# design.net
KiCad netlist of a schematic drawn in Altium Designer
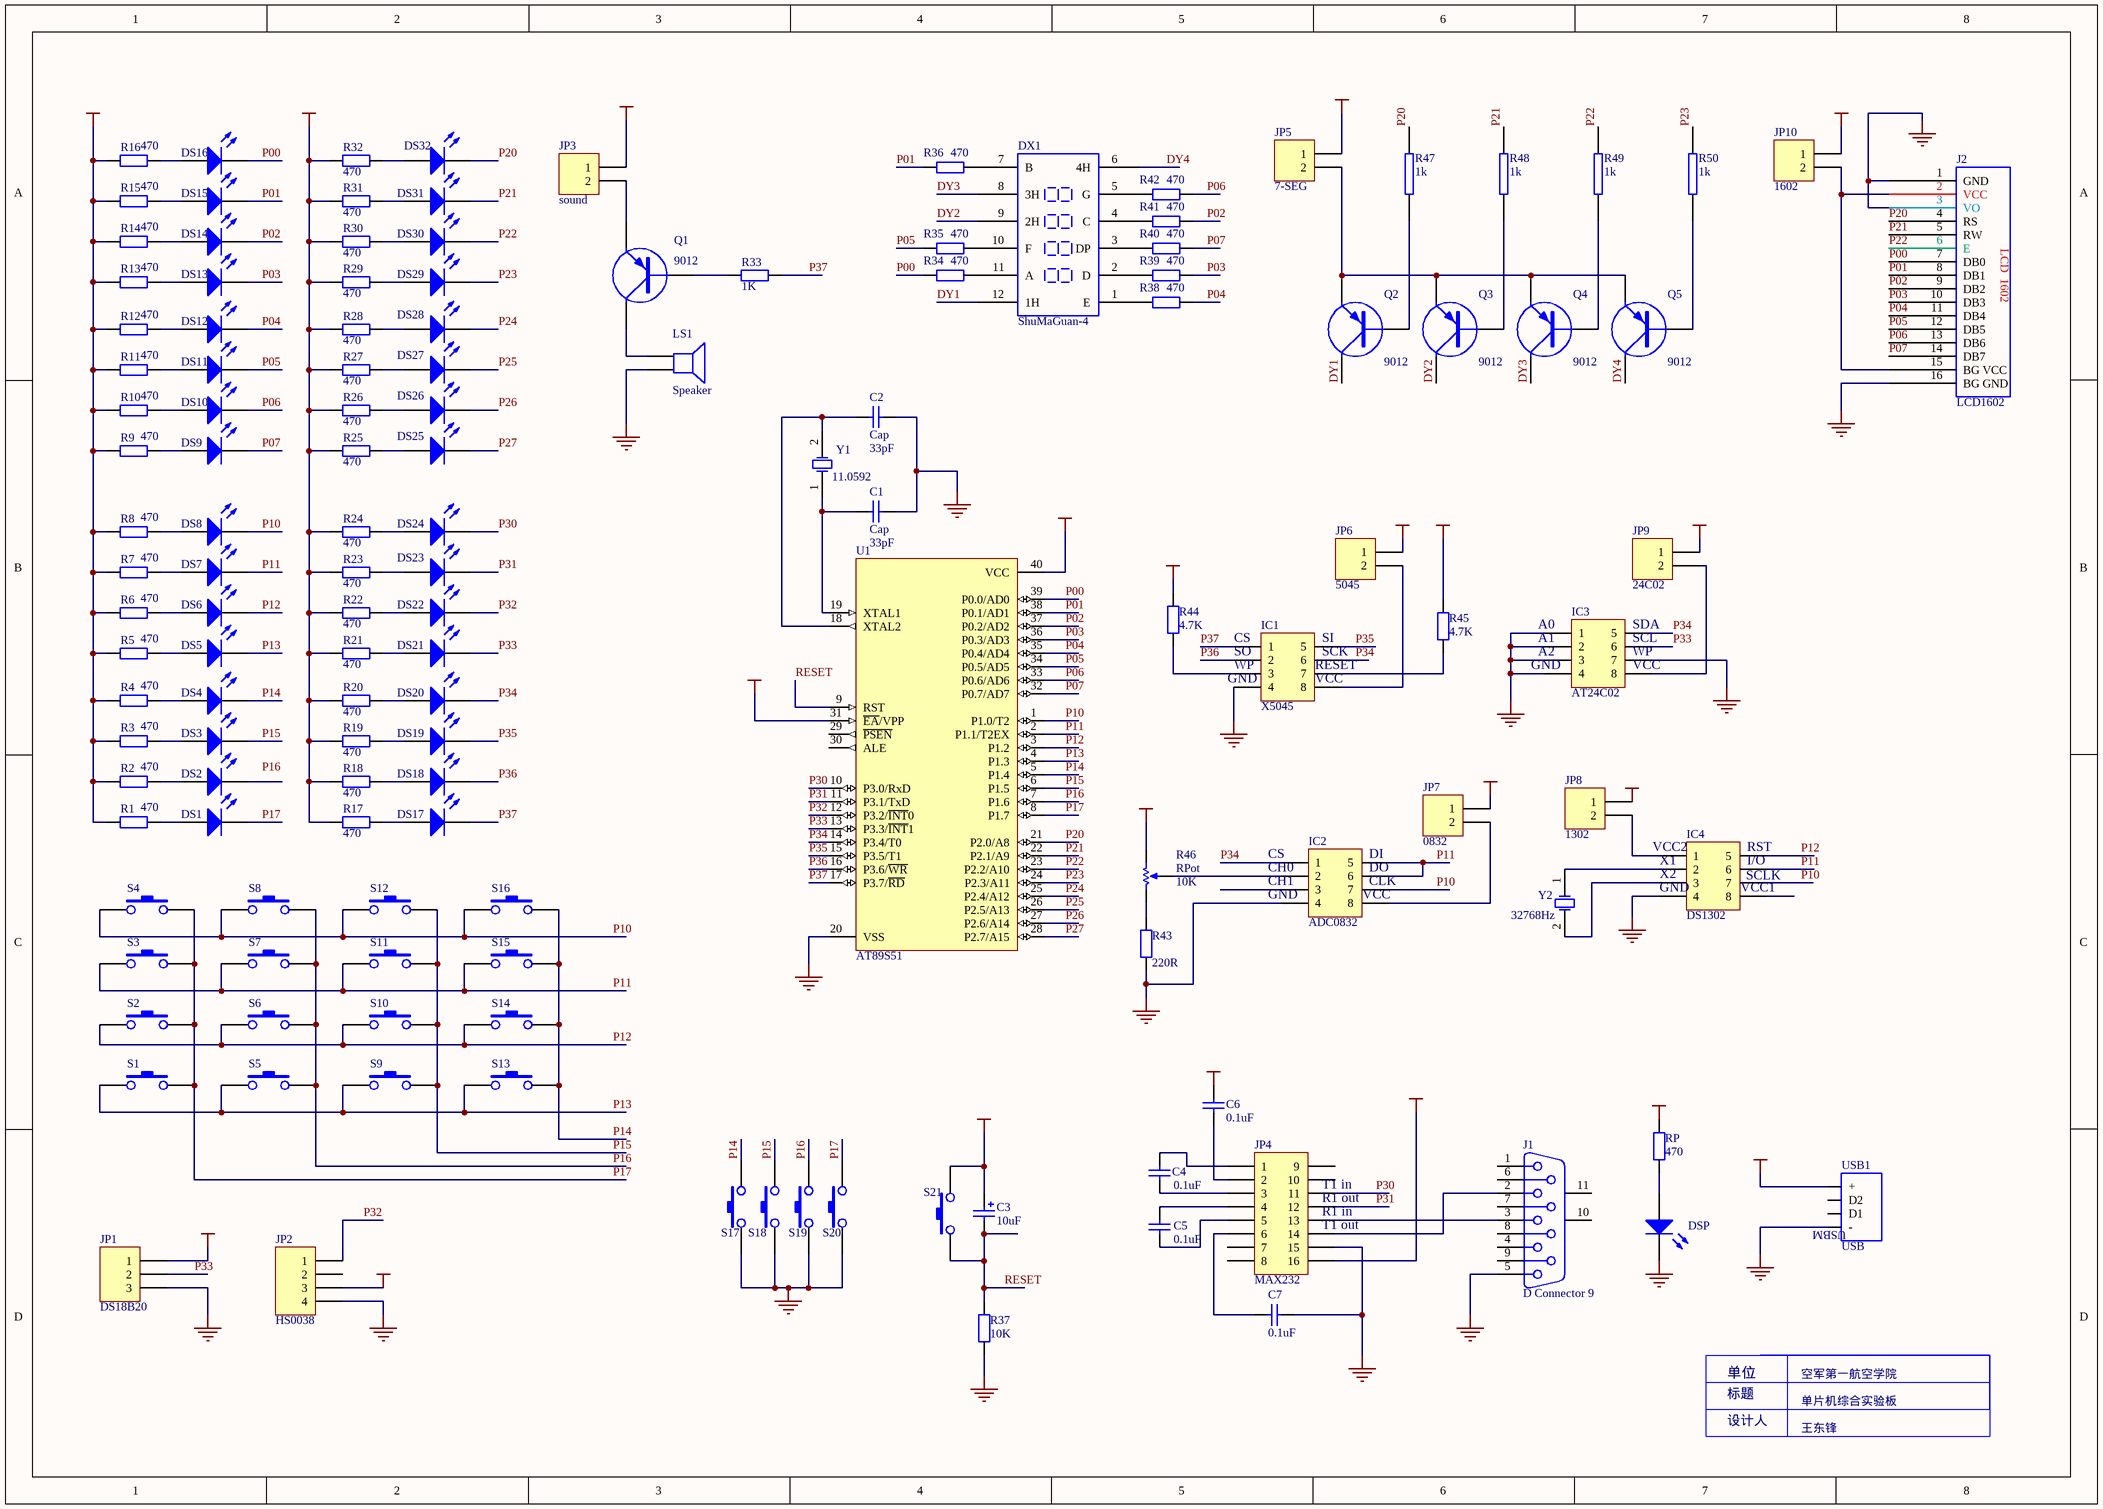
[diagram p0: 配套实验板原理图.SchDoc]

(export (version "E")
  (design (tool "Eeschema 10.0.6"))
  (components
    (comp (ref "C1")
      (value "Cap")
      (footprint "RAD-0.1")
      (description "Capacitor")
      (fields (field (name "ALTIUM_VALUE") "33pF") (field (name "PUBLISHER") "Altium Limited"))
      (libsource (lib "Miscellaneous Devices") (part "Cap"))
    )
    (comp (ref "C2")
      (value "Cap")
      (footprint "RAD-0.1")
      (description "Capacitor")
      (fields (field (name "ALTIUM_VALUE") "33pF") (field (name "PUBLISHER") "Altium Limited"))
      (libsource (lib "Miscellaneous Devices") (part "Cap"))
    )
    (comp (ref "C3")
      (value "10uF")
      (footprint "CAPPR2-5X6.8")
      (description "Polarized Capacitor (Radial)")
      (fields (field (name "PUBLISHER") "Altium Limited"))
      (libsource (lib "Miscellaneous Devices") (part "Cap Pol1"))
    )
    (comp (ref "C4")
      (value "0.1uF")
      (footprint "RAD-0.1")
      (description "Capacitor")
      (fields (field (name "PUBLISHER") "Altium Limited"))
      (libsource (lib "Miscellaneous Devices") (part "Cap"))
    )
    (comp (ref "C5")
      (value "0.1uF")
      (footprint "RAD-0.1")
      (description "Capacitor")
      (fields (field (name "PUBLISHER") "Altium Limited"))
      (libsource (lib "Miscellaneous Devices") (part "Cap"))
    )
    (comp (ref "C6")
      (value "0.1uF")
      (footprint "RAD-0.1")
      (description "Capacitor")
      (fields (field (name "PUBLISHER") "Altium Limited"))
      (libsource (lib "Miscellaneous Devices") (part "Cap"))
    )
    (comp (ref "C7")
      (value "0.1uF")
      (footprint "RAD-0.1")
      (description "Capacitor")
      (fields (field (name "PUBLISHER") "Altium Limited"))
      (libsource (lib "Miscellaneous Devices") (part "Cap"))
    )
    (comp (ref "DS1")
      (value "~")
      (footprint "CAPPR2-5X6.8")
      (description "Typical INFRARED GaAs LED")
      (fields (field (name "PUBLISHER") "Altium Limited"))
      (libsource (lib "Miscellaneous Devices") (part "LED0"))
    )
    (comp (ref "DS2")
      (value "~")
      (footprint "CAPPR2-5X6.8")
      (description "Typical INFRARED GaAs LED")
      (fields (field (name "PUBLISHER") "Altium Limited"))
      (libsource (lib "Miscellaneous Devices") (part "LED0"))
    )
    (comp (ref "DS3")
      (value "~")
      (footprint "CAPPR2-5X6.8")
      (description "Typical INFRARED GaAs LED")
      (fields (field (name "PUBLISHER") "Altium Limited"))
      (libsource (lib "Miscellaneous Devices") (part "LED0"))
    )
    (comp (ref "DS4")
      (value "~")
      (footprint "CAPPR2-5X6.8")
      (description "Typical INFRARED GaAs LED")
      (fields (field (name "PUBLISHER") "Altium Limited"))
      (libsource (lib "Miscellaneous Devices") (part "LED0"))
    )
    (comp (ref "DS5")
      (value "~")
      (footprint "CAPPR2-5X6.8")
      (description "Typical INFRARED GaAs LED")
      (fields (field (name "PUBLISHER") "Altium Limited"))
      (libsource (lib "Miscellaneous Devices") (part "LED0"))
    )
    (comp (ref "DS6")
      (value "~")
      (footprint "CAPPR2-5X6.8")
      (description "Typical INFRARED GaAs LED")
      (fields (field (name "PUBLISHER") "Altium Limited"))
      (libsource (lib "Miscellaneous Devices") (part "LED0"))
    )
    (comp (ref "DS7")
      (value "~")
      (footprint "CAPPR2-5X6.8")
      (description "Typical INFRARED GaAs LED")
      (fields (field (name "PUBLISHER") "Altium Limited"))
      (libsource (lib "Miscellaneous Devices") (part "LED0"))
    )
    (comp (ref "DS8")
      (value "~")
      (footprint "CAPPR2-5X6.8")
      (description "Typical INFRARED GaAs LED")
      (fields (field (name "PUBLISHER") "Altium Limited"))
      (libsource (lib "Miscellaneous Devices") (part "LED0"))
    )
    (comp (ref "DS9")
      (value "~")
      (footprint "CAPPR2-5X6.8")
      (description "Typical INFRARED GaAs LED")
      (fields (field (name "PUBLISHER") "Altium Limited"))
      (libsource (lib "Miscellaneous Devices") (part "LED0"))
    )
    (comp (ref "DS10")
      (value "~")
      (footprint "CAPPR2-5X6.8")
      (description "Typical INFRARED GaAs LED")
      (fields (field (name "PUBLISHER") "Altium Limited"))
      (libsource (lib "Miscellaneous Devices") (part "LED0"))
    )
    (comp (ref "DS11")
      (value "~")
      (footprint "CAPPR2-5X6.8")
      (description "Typical INFRARED GaAs LED")
      (fields (field (name "PUBLISHER") "Altium Limited"))
      (libsource (lib "Miscellaneous Devices") (part "LED0"))
    )
    (comp (ref "DS12")
      (value "~")
      (footprint "CAPPR2-5X6.8")
      (description "Typical INFRARED GaAs LED")
      (fields (field (name "PUBLISHER") "Altium Limited"))
      (libsource (lib "Miscellaneous Devices") (part "LED0"))
    )
    (comp (ref "DS13")
      (value "~")
      (footprint "CAPPR2-5X6.8")
      (description "Typical INFRARED GaAs LED")
      (fields (field (name "PUBLISHER") "Altium Limited"))
      (libsource (lib "Miscellaneous Devices") (part "LED0"))
    )
    (comp (ref "DS14")
      (value "~")
      (footprint "CAPPR2-5X6.8")
      (description "Typical INFRARED GaAs LED")
      (fields (field (name "PUBLISHER") "Altium Limited"))
      (libsource (lib "Miscellaneous Devices") (part "LED0"))
    )
    (comp (ref "DS15")
      (value "~")
      (footprint "CAPPR2-5X6.8")
      (description "Typical INFRARED GaAs LED")
      (fields (field (name "PUBLISHER") "Altium Limited"))
      (libsource (lib "Miscellaneous Devices") (part "LED0"))
    )
    (comp (ref "DS16")
      (value "~")
      (footprint "CAPPR2-5X6.8")
      (description "Typical INFRARED GaAs LED")
      (fields (field (name "PUBLISHER") "Altium Limited"))
      (libsource (lib "Miscellaneous Devices") (part "LED0"))
    )
    (comp (ref "DS17")
      (value "~")
      (footprint "CAPPR2-5X6.8")
      (description "Typical INFRARED GaAs LED")
      (fields (field (name "PUBLISHER") "Altium Limited"))
      (libsource (lib "Miscellaneous Devices") (part "LED0"))
    )
    (comp (ref "DS18")
      (value "~")
      (footprint "CAPPR2-5X6.8")
      (description "Typical INFRARED GaAs LED")
      (fields (field (name "PUBLISHER") "Altium Limited"))
      (libsource (lib "Miscellaneous Devices") (part "LED0"))
    )
    (comp (ref "DS19")
      (value "~")
      (footprint "CAPPR2-5X6.8")
      (description "Typical INFRARED GaAs LED")
      (fields (field (name "PUBLISHER") "Altium Limited"))
      (libsource (lib "Miscellaneous Devices") (part "LED0"))
    )
    (comp (ref "DS20")
      (value "~")
      (footprint "CAPPR2-5X6.8")
      (description "Typical INFRARED GaAs LED")
      (fields (field (name "PUBLISHER") "Altium Limited"))
      (libsource (lib "Miscellaneous Devices") (part "LED0"))
    )
    (comp (ref "DS21")
      (value "~")
      (footprint "CAPPR2-5X6.8")
      (description "Typical INFRARED GaAs LED")
      (fields (field (name "PUBLISHER") "Altium Limited"))
      (libsource (lib "Miscellaneous Devices") (part "LED0"))
    )
    (comp (ref "DS22")
      (value "~")
      (footprint "CAPPR2-5X6.8")
      (description "Typical INFRARED GaAs LED")
      (fields (field (name "PUBLISHER") "Altium Limited"))
      (libsource (lib "Miscellaneous Devices") (part "LED0"))
    )
    (comp (ref "DS23")
      (value "~")
      (footprint "CAPPR2-5X6.8")
      (description "Typical INFRARED GaAs LED")
      (fields (field (name "PUBLISHER") "Altium Limited"))
      (libsource (lib "Miscellaneous Devices") (part "LED0"))
    )
    (comp (ref "DS24")
      (value "~")
      (footprint "CAPPR2-5X6.8")
      (description "Typical INFRARED GaAs LED")
      (fields (field (name "PUBLISHER") "Altium Limited"))
      (libsource (lib "Miscellaneous Devices") (part "LED0"))
    )
    (comp (ref "DS25")
      (value "~")
      (footprint "CAPPR2-5X6.8")
      (description "Typical INFRARED GaAs LED")
      (fields (field (name "PUBLISHER") "Altium Limited"))
      (libsource (lib "Miscellaneous Devices") (part "LED0"))
    )
    (comp (ref "DS26")
      (value "~")
      (footprint "CAPPR2-5X6.8")
      (description "Typical INFRARED GaAs LED")
      (fields (field (name "PUBLISHER") "Altium Limited"))
      (libsource (lib "Miscellaneous Devices") (part "LED0"))
    )
    (comp (ref "DS27")
      (value "~")
      (footprint "CAPPR2-5X6.8")
      (description "Typical INFRARED GaAs LED")
      (fields (field (name "PUBLISHER") "Altium Limited"))
      (libsource (lib "Miscellaneous Devices") (part "LED0"))
    )
    (comp (ref "DS28")
      (value "~")
      (footprint "CAPPR2-5X6.8")
      (description "Typical INFRARED GaAs LED")
      (fields (field (name "PUBLISHER") "Altium Limited"))
      (libsource (lib "Miscellaneous Devices") (part "LED0"))
    )
    (comp (ref "DS29")
      (value "~")
      (footprint "CAPPR2-5X6.8")
      (description "Typical INFRARED GaAs LED")
      (fields (field (name "PUBLISHER") "Altium Limited"))
      (libsource (lib "Miscellaneous Devices") (part "LED0"))
    )
    (comp (ref "DS30")
      (value "~")
      (footprint "CAPPR2-5X6.8")
      (description "Typical INFRARED GaAs LED")
      (fields (field (name "PUBLISHER") "Altium Limited"))
      (libsource (lib "Miscellaneous Devices") (part "LED0"))
    )
    (comp (ref "DS31")
      (value "~")
      (footprint "CAPPR2-5X6.8")
      (description "Typical INFRARED GaAs LED")
      (fields (field (name "PUBLISHER") "Altium Limited"))
      (libsource (lib "Miscellaneous Devices") (part "LED0"))
    )
    (comp (ref "DS32")
      (value "~")
      (footprint "CAPPR2-5X6.8")
      (description "Typical INFRARED GaAs LED")
      (fields (field (name "PUBLISHER") "Altium Limited"))
      (libsource (lib "Miscellaneous Devices") (part "LED0"))
    )
    (comp (ref "DSP")
      (value "~")
      (footprint "CAPPR2-5X6.8")
      (description "Typical INFRARED GaAs LED")
      (fields (field (name "PUBLISHER") "Altium Limited"))
      (libsource (lib "Miscellaneous Devices") (part "LED0"))
    )
    (comp (ref "DX1") (value "ShuMaGuan-4") (footprint "DIP12 - duplicate") (libsource (lib "*") (part "84")))
    (comp (ref "IC1")
      (value "X5045")
      (footprint "DIP-8")
      (description "Header, 4-Pin, Dual row")
      (fields (field (name "PUBLISHER") "Altium Limited"))
      (libsource (lib "Miscellaneous Connectors") (part "Header 4X2A"))
    )
    (comp (ref "IC2")
      (value "ADC0832")
      (footprint "DIP-8")
      (description "Header, 4-Pin, Dual row")
      (fields (field (name "PUBLISHER") "Altium Limited"))
      (libsource (lib "Miscellaneous Connectors") (part "Header 4X2A"))
    )
    (comp (ref "IC3")
      (value "AT24C02")
      (footprint "DIP-8")
      (description "Header, 4-Pin, Dual row")
      (fields (field (name "PUBLISHER") "Altium Limited"))
      (libsource (lib "Miscellaneous Connectors") (part "Header 4X2A"))
    )
    (comp (ref "IC4")
      (value "DS1302")
      (footprint "DIP-8")
      (description "Header, 4-Pin, Dual row")
      (fields (field (name "PUBLISHER") "Altium Limited"))
      (libsource (lib "Miscellaneous Connectors") (part "Header 4X2A"))
    )
    (comp (ref "J1")
      (value "D Connector 9")
      (footprint "DSUB1.385-2H9")
      (description "Receptacle Assembly, 9 Position, Right Angle")
      (fields (field (name "PUBLISHER") "Altium Limited"))
      (libsource (lib "Miscellaneous Connectors") (part "D Connector 9"))
    )
    (comp (ref "J2") (value "LCD1602") (footprint "HDR1X16") (libsource (lib "我的原理图库") (part "LCD1602")))
    (comp (ref "JP1")
      (value "DS18B20")
      (footprint "HDR1X3")
      (description "Header, 3-Pin")
      (fields (field (name "PUBLISHER") "Altium Limited"))
      (libsource (lib "Miscellaneous Connectors") (part "Header 3"))
    )
    (comp (ref "JP2")
      (value "HS0038")
      (footprint "HDR1X4")
      (description "Header, 4-Pin")
      (fields (field (name "PUBLISHER") "Altium Limited"))
      (libsource (lib "Miscellaneous Connectors") (part "Header 4"))
    )
    (comp (ref "JP3")
      (value "sound")
      (footprint "HDR1X2")
      (description "Header, 2-Pin")
      (fields (field (name "PUBLISHER") "Altium Limited"))
      (libsource (lib "Miscellaneous Connectors") (part "Header 2"))
    )
    (comp (ref "JP4")
      (value "MAX232")
      (footprint "DIP-16")
      (description "Header, 8-Pin, Dual row")
      (fields (field (name "PUBLISHER") "Altium Limited"))
      (libsource (lib "Miscellaneous Connectors") (part "Header 8X2A"))
    )
    (comp (ref "JP5")
      (value "7-SEG")
      (footprint "HDR1X2")
      (description "Header, 2-Pin")
      (fields (field (name "PUBLISHER") "Altium Limited"))
      (libsource (lib "Miscellaneous Connectors") (part "Header 2"))
    )
    (comp (ref "JP6")
      (value "5045")
      (footprint "HDR1X2")
      (description "Header, 2-Pin")
      (fields (field (name "PUBLISHER") "Altium Limited"))
      (libsource (lib "Miscellaneous Connectors") (part "Header 2"))
    )
    (comp (ref "JP7")
      (value "0832")
      (footprint "HDR1X2")
      (description "Header, 2-Pin")
      (fields (field (name "PUBLISHER") "Altium Limited"))
      (libsource (lib "Miscellaneous Connectors") (part "Header 2"))
    )
    (comp (ref "JP8")
      (value "1302")
      (footprint "HDR1X2")
      (description "Header, 2-Pin")
      (fields (field (name "PUBLISHER") "Altium Limited"))
      (libsource (lib "Miscellaneous Connectors") (part "Header 2"))
    )
    (comp (ref "JP9")
      (value "24C02")
      (footprint "HDR1X2")
      (description "Header, 2-Pin")
      (fields (field (name "PUBLISHER") "Altium Limited"))
      (libsource (lib "Miscellaneous Connectors") (part "Header 2"))
    )
    (comp (ref "JP10")
      (value "1602")
      (footprint "HDR1X2")
      (description "Header, 2-Pin")
      (fields (field (name "PUBLISHER") "Altium Limited"))
      (libsource (lib "Miscellaneous Connectors") (part "Header 2"))
    )
    (comp (ref "LS1")
      (value "Speaker")
      (footprint "spk")
      (description "Loudspeaker")
      (fields (field (name "PUBLISHER") "Altium Limited"))
      (libsource (lib "Miscellaneous Devices") (part "Speaker"))
    )
    (comp (ref "Q1")
      (value "9012")
      (footprint "MJT")
      (description "PNP Transistor")
      (libsource (lib "常用原理图元件库") (part "PNP"))
    )
    (comp (ref "Q2")
      (value "9012")
      (footprint "MJT")
      (description "PNP Transistor")
      (libsource (lib "*") (part "PNP"))
    )
    (comp (ref "Q3")
      (value "9012")
      (footprint "MJT")
      (description "PNP Transistor")
      (libsource (lib "*") (part "PNP"))
    )
    (comp (ref "Q4")
      (value "9012")
      (footprint "MJT")
      (description "PNP Transistor")
      (libsource (lib "*") (part "PNP"))
    )
    (comp (ref "Q5")
      (value "9012")
      (footprint "MJT")
      (description "PNP Transistor")
      (libsource (lib "*") (part "PNP"))
    )
    (comp (ref "R1")
      (value "470")
      (footprint "AXIAL-0.4")
      (description "Resistor")
      (fields (field (name "PUBLISHER") "Altium Limited"))
      (libsource (lib "Miscellaneous Devices") (part "Res2"))
    )
    (comp (ref "R2")
      (value "470")
      (footprint "AXIAL-0.4")
      (description "Resistor")
      (fields (field (name "PUBLISHER") "Altium Limited"))
      (libsource (lib "Miscellaneous Devices") (part "Res2"))
    )
    (comp (ref "R3")
      (value "470")
      (footprint "AXIAL-0.4")
      (description "Resistor")
      (fields (field (name "PUBLISHER") "Altium Limited"))
      (libsource (lib "Miscellaneous Devices") (part "Res2"))
    )
    (comp (ref "R4")
      (value "470")
      (footprint "AXIAL-0.4")
      (description "Resistor")
      (fields (field (name "PUBLISHER") "Altium Limited"))
      (libsource (lib "Miscellaneous Devices") (part "Res2"))
    )
    (comp (ref "R5")
      (value "470")
      (footprint "AXIAL-0.4")
      (description "Resistor")
      (fields (field (name "PUBLISHER") "Altium Limited"))
      (libsource (lib "Miscellaneous Devices") (part "Res2"))
    )
    (comp (ref "R6")
      (value "470")
      (footprint "AXIAL-0.4")
      (description "Resistor")
      (fields (field (name "PUBLISHER") "Altium Limited"))
      (libsource (lib "Miscellaneous Devices") (part "Res2"))
    )
    (comp (ref "R7")
      (value "470")
      (footprint "AXIAL-0.4")
      (description "Resistor")
      (fields (field (name "PUBLISHER") "Altium Limited"))
      (libsource (lib "Miscellaneous Devices") (part "Res2"))
    )
    (comp (ref "R8")
      (value "470")
      (footprint "AXIAL-0.4")
      (description "Resistor")
      (fields (field (name "PUBLISHER") "Altium Limited"))
      (libsource (lib "Miscellaneous Devices") (part "Res2"))
    )
    (comp (ref "R9")
      (value "470")
      (footprint "AXIAL-0.4")
      (description "Resistor")
      (fields (field (name "PUBLISHER") "Altium Limited"))
      (libsource (lib "Miscellaneous Devices") (part "Res2"))
    )
    (comp (ref "R10")
      (value "470")
      (footprint "AXIAL-0.4")
      (description "Resistor")
      (fields (field (name "PUBLISHER") "Altium Limited"))
      (libsource (lib "Miscellaneous Devices") (part "Res2"))
    )
    (comp (ref "R11")
      (value "470")
      (footprint "AXIAL-0.4")
      (description "Resistor")
      (fields (field (name "PUBLISHER") "Altium Limited"))
      (libsource (lib "Miscellaneous Devices") (part "Res2"))
    )
    (comp (ref "R12")
      (value "470")
      (footprint "AXIAL-0.4")
      (description "Resistor")
      (fields (field (name "PUBLISHER") "Altium Limited"))
      (libsource (lib "Miscellaneous Devices") (part "Res2"))
    )
    (comp (ref "R13")
      (value "470")
      (footprint "AXIAL-0.4")
      (description "Resistor")
      (fields (field (name "PUBLISHER") "Altium Limited"))
      (libsource (lib "Miscellaneous Devices") (part "Res2"))
    )
    (comp (ref "R14")
      (value "470")
      (footprint "AXIAL-0.4")
      (description "Resistor")
      (fields (field (name "PUBLISHER") "Altium Limited"))
      (libsource (lib "Miscellaneous Devices") (part "Res2"))
    )
    (comp (ref "R15")
      (value "470")
      (footprint "AXIAL-0.4")
      (description "Resistor")
      (fields (field (name "PUBLISHER") "Altium Limited"))
      (libsource (lib "Miscellaneous Devices") (part "Res2"))
    )
    (comp (ref "R16")
      (value "470")
      (footprint "AXIAL-0.4")
      (description "Resistor")
      (fields (field (name "PUBLISHER") "Altium Limited"))
      (libsource (lib "Miscellaneous Devices") (part "Res2"))
    )
    (comp (ref "R17")
      (value "470")
      (footprint "AXIAL-0.4")
      (description "Resistor")
      (fields (field (name "PUBLISHER") "Altium Limited"))
      (libsource (lib "Miscellaneous Devices") (part "Res2"))
    )
    (comp (ref "R18")
      (value "470")
      (footprint "AXIAL-0.4")
      (description "Resistor")
      (fields (field (name "PUBLISHER") "Altium Limited"))
      (libsource (lib "Miscellaneous Devices") (part "Res2"))
    )
    (comp (ref "R19")
      (value "470")
      (footprint "AXIAL-0.4")
      (description "Resistor")
      (fields (field (name "PUBLISHER") "Altium Limited"))
      (libsource (lib "Miscellaneous Devices") (part "Res2"))
    )
    (comp (ref "R20")
      (value "470")
      (footprint "AXIAL-0.4")
      (description "Resistor")
      (fields (field (name "PUBLISHER") "Altium Limited"))
      (libsource (lib "Miscellaneous Devices") (part "Res2"))
    )
    (comp (ref "R21")
      (value "470")
      (footprint "AXIAL-0.4")
      (description "Resistor")
      (fields (field (name "PUBLISHER") "Altium Limited"))
      (libsource (lib "Miscellaneous Devices") (part "Res2"))
    )
    (comp (ref "R22")
      (value "470")
      (footprint "AXIAL-0.4")
      (description "Resistor")
      (fields (field (name "PUBLISHER") "Altium Limited"))
      (libsource (lib "Miscellaneous Devices") (part "Res2"))
    )
    (comp (ref "R23")
      (value "470")
      (footprint "AXIAL-0.4")
      (description "Resistor")
      (fields (field (name "PUBLISHER") "Altium Limited"))
      (libsource (lib "Miscellaneous Devices") (part "Res2"))
    )
    (comp (ref "R24")
      (value "470")
      (footprint "AXIAL-0.4")
      (description "Resistor")
      (fields (field (name "PUBLISHER") "Altium Limited"))
      (libsource (lib "Miscellaneous Devices") (part "Res2"))
    )
    (comp (ref "R25")
      (value "470")
      (footprint "AXIAL-0.4")
      (description "Resistor")
      (fields (field (name "PUBLISHER") "Altium Limited"))
      (libsource (lib "Miscellaneous Devices") (part "Res2"))
    )
    (comp (ref "R26")
      (value "470")
      (footprint "AXIAL-0.4")
      (description "Resistor")
      (fields (field (name "PUBLISHER") "Altium Limited"))
      (libsource (lib "Miscellaneous Devices") (part "Res2"))
    )
    (comp (ref "R27")
      (value "470")
      (footprint "AXIAL-0.4")
      (description "Resistor")
      (fields (field (name "PUBLISHER") "Altium Limited"))
      (libsource (lib "Miscellaneous Devices") (part "Res2"))
    )
    (comp (ref "R28")
      (value "470")
      (footprint "AXIAL-0.4")
      (description "Resistor")
      (fields (field (name "PUBLISHER") "Altium Limited"))
      (libsource (lib "Miscellaneous Devices") (part "Res2"))
    )
    (comp (ref "R29")
      (value "470")
      (footprint "AXIAL-0.4")
      (description "Resistor")
      (fields (field (name "PUBLISHER") "Altium Limited"))
      (libsource (lib "Miscellaneous Devices") (part "Res2"))
    )
    (comp (ref "R30")
      (value "470")
      (footprint "AXIAL-0.4")
      (description "Resistor")
      (fields (field (name "PUBLISHER") "Altium Limited"))
      (libsource (lib "Miscellaneous Devices") (part "Res2"))
    )
    (comp (ref "R31")
      (value "470")
      (footprint "AXIAL-0.4")
      (description "Resistor")
      (fields (field (name "PUBLISHER") "Altium Limited"))
      (libsource (lib "Miscellaneous Devices") (part "Res2"))
    )
    (comp (ref "R32")
      (value "470")
      (footprint "AXIAL-0.4")
      (description "Resistor")
      (fields (field (name "PUBLISHER") "Altium Limited"))
      (libsource (lib "Miscellaneous Devices") (part "Res2"))
    )
    (comp (ref "R33")
      (value "1K")
      (footprint "AXIAL-0.4")
      (description "Resistor")
      (fields (field (name "PUBLISHER") "Altium Limited"))
      (libsource (lib "Miscellaneous Devices") (part "Res2"))
    )
    (comp (ref "R34")
      (value "470")
      (footprint "AXIAL-0.4")
      (description "Resistor")
      (fields (field (name "PUBLISHER") "Altium Limited"))
      (libsource (lib "Miscellaneous Devices") (part "Res2"))
    )
    (comp (ref "R35")
      (value "470")
      (footprint "AXIAL-0.4")
      (description "Resistor")
      (fields (field (name "PUBLISHER") "Altium Limited"))
      (libsource (lib "Miscellaneous Devices") (part "Res2"))
    )
    (comp (ref "R36")
      (value "470")
      (footprint "AXIAL-0.4")
      (description "Resistor")
      (fields (field (name "PUBLISHER") "Altium Limited"))
      (libsource (lib "Miscellaneous Devices") (part "Res2"))
    )
    (comp (ref "R37")
      (value "10K")
      (footprint "AXIAL-0.4")
      (description "Resistor")
      (fields (field (name "PUBLISHER") "Altium Limited"))
      (libsource (lib "") (part "Res2_1"))
    )
    (comp (ref "R38")
      (value "470")
      (footprint "AXIAL-0.4")
      (description "Resistor")
      (fields (field (name "PUBLISHER") "Altium Limited"))
      (libsource (lib "Miscellaneous Devices") (part "Res2"))
    )
    (comp (ref "R39")
      (value "470")
      (footprint "AXIAL-0.4")
      (description "Resistor")
      (fields (field (name "PUBLISHER") "Altium Limited"))
      (libsource (lib "Miscellaneous Devices") (part "Res2"))
    )
    (comp (ref "R40")
      (value "470")
      (footprint "AXIAL-0.4")
      (description "Resistor")
      (fields (field (name "PUBLISHER") "Altium Limited"))
      (libsource (lib "Miscellaneous Devices") (part "Res2"))
    )
    (comp (ref "R41")
      (value "470")
      (footprint "AXIAL-0.4")
      (description "Resistor")
      (fields (field (name "PUBLISHER") "Altium Limited"))
      (libsource (lib "Miscellaneous Devices") (part "Res2"))
    )
    (comp (ref "R42")
      (value "470")
      (footprint "AXIAL-0.4")
      (description "Resistor")
      (fields (field (name "PUBLISHER") "Altium Limited"))
      (libsource (lib "Miscellaneous Devices") (part "Res2"))
    )
    (comp (ref "R43")
      (value "220R")
      (footprint "AXIAL-0.4")
      (description "Resistor")
      (fields (field (name "PUBLISHER") "Altium Limited"))
      (libsource (lib "") (part "Res2_1"))
    )
    (comp (ref "R44")
      (value "4.7K")
      (footprint "AXIAL-0.4")
      (description "Resistor")
      (fields (field (name "PUBLISHER") "Altium Limited"))
      (libsource (lib "") (part "Res2_1"))
    )
    (comp (ref "R45")
      (value "4.7K")
      (footprint "AXIAL-0.4")
      (description "Resistor")
      (fields (field (name "PUBLISHER") "Altium Limited"))
      (libsource (lib "") (part "Res2_1"))
    )
    (comp (ref "R46")
      (value "RPot")
      (footprint "VR4")
      (description "Potentiometer")
      (fields (field (name "ALTIUM_VALUE") "10K") (field (name "PUBLISHER") "Altium Limited"))
      (libsource (lib "Miscellaneous Devices") (part "RPot"))
    )
    (comp (ref "R47") (value "1k") (footprint "AXIAL-0.4") (libsource (lib "*") (part "RES2")))
    (comp (ref "R48") (value "1k") (footprint "AXIAL-0.4") (libsource (lib "*") (part "RES2")))
    (comp (ref "R49") (value "1k") (footprint "AXIAL-0.4") (libsource (lib "*") (part "RES2")))
    (comp (ref "R50") (value "1k") (footprint "AXIAL-0.4") (libsource (lib "*") (part "RES2")))
    (comp (ref "RP")
      (value "470")
      (footprint "AXIAL-0.4")
      (description "Resistor")
      (fields (field (name "PUBLISHER") "Altium Limited"))
      (libsource (lib "") (part "Res2_2"))
    )
    (comp (ref "S1") (value "~") (footprint "AN") (libsource (lib "常用原理图元件库") (part "SW-PB")))
    (comp (ref "S2") (value "~") (footprint "AN") (libsource (lib "常用原理图元件库") (part "SW-PB")))
    (comp (ref "S3") (value "~") (footprint "AN") (libsource (lib "常用原理图元件库") (part "SW-PB")))
    (comp (ref "S4") (value "~") (footprint "AN") (libsource (lib "常用原理图元件库") (part "SW-PB")))
    (comp (ref "S5") (value "~") (footprint "AN") (libsource (lib "常用原理图元件库") (part "SW-PB")))
    (comp (ref "S6") (value "~") (footprint "AN") (libsource (lib "常用原理图元件库") (part "SW-PB")))
    (comp (ref "S7") (value "~") (footprint "AN") (libsource (lib "常用原理图元件库") (part "SW-PB")))
    (comp (ref "S8") (value "~") (footprint "AN") (libsource (lib "常用原理图元件库") (part "SW-PB")))
    (comp (ref "S9") (value "~") (footprint "AN") (libsource (lib "常用原理图元件库") (part "SW-PB")))
    (comp (ref "S10") (value "~") (footprint "AN") (libsource (lib "常用原理图元件库") (part "SW-PB")))
    (comp (ref "S11") (value "~") (footprint "AN") (libsource (lib "常用原理图元件库") (part "SW-PB")))
    (comp (ref "S12") (value "~") (footprint "AN") (libsource (lib "常用原理图元件库") (part "SW-PB")))
    (comp (ref "S13") (value "~") (footprint "AN") (libsource (lib "常用原理图元件库") (part "SW-PB")))
    (comp (ref "S14") (value "~") (footprint "AN") (libsource (lib "常用原理图元件库") (part "SW-PB")))
    (comp (ref "S15") (value "~") (footprint "AN") (libsource (lib "常用原理图元件库") (part "SW-PB")))
    (comp (ref "S16") (value "~") (footprint "AN") (libsource (lib "常用原理图元件库") (part "SW-PB")))
    (comp (ref "S17") (value "~") (footprint "AN") (libsource (lib "常用原理图元件库") (part "SW-PB")))
    (comp (ref "S18") (value "~") (footprint "AN") (libsource (lib "常用原理图元件库") (part "SW-PB")))
    (comp (ref "S19") (value "~") (footprint "AN") (libsource (lib "常用原理图元件库") (part "SW-PB")))
    (comp (ref "S20") (value "~") (footprint "AN") (libsource (lib "常用原理图元件库") (part "SW-PB")))
    (comp (ref "S21") (value "~") (footprint "AN") (libsource (lib "常用原理图元件库") (part "SW-PB")))
    (comp (ref "U1")
      (value "AT89S51")
      (footprint "SOT129-1")
      (description "80C51 8-Bit Flash Microcontroller Family, 32 kB Flash")
      (fields (field (name "PUBLISHER") "Altium Limited"))
      (libsource (lib "Philips Microcontroller 8-Bit") (part "P89C58X2BN"))
    )
    (comp (ref "USB1") (value "USB") (footprint "USB") (libsource (lib "BianChengQi") (part "USB")))
    (comp (ref "Y1")
      (value "11.0592")
      (footprint "RAD-0.2")
      (description "Crystal Oscillator")
      (fields (field (name "PUBLISHER") "Altium Limited"))
      (libsource (lib "Miscellaneous Devices") (part "XTAL"))
    )
    (comp (ref "Y2")
      (value "32768Hz")
      (footprint "RAD-0.2")
      (description "Crystal Oscillator")
      (fields (field (name "PUBLISHER") "Altium Limited"))
      (libsource (lib "Miscellaneous Devices") (part "XTAL"))
    )
  )
  (nets
    (net (code "1") (name "/DY1") (class "Default")
      (node (ref "DX1") (pin "12") (pinfunction "1H_12") (pintype "passive"))
      (node (ref "Q2") (pin "3") (pinfunction "C_3") (pintype "passive"))
    )
    (net (code "2") (name "/DY2") (class "Default")
      (node (ref "DX1") (pin "9") (pinfunction "2H_9") (pintype "passive"))
      (node (ref "Q3") (pin "3") (pinfunction "C_3") (pintype "passive"))
    )
    (net (code "3") (name "/DY3") (class "Default")
      (node (ref "DX1") (pin "8") (pinfunction "3H_8") (pintype "passive"))
      (node (ref "Q4") (pin "3") (pinfunction "C_3") (pintype "passive"))
    )
    (net (code "4") (name "/DY4") (class "Default")
      (node (ref "DX1") (pin "6") (pinfunction "4H_6") (pintype "passive"))
      (node (ref "Q5") (pin "3") (pinfunction "C_3") (pintype "passive"))
    )
    (net (code "5") (name "/P00") (class "Default")
      (node (ref "DS16") (pin "2") (pinfunction "K_2") (pintype "passive"))
      (node (ref "J2") (pin "7") (pinfunction "DB0_7") (pintype "passive"))
      (node (ref "R34") (pin "1") (pinfunction "1_1") (pintype "passive"))
      (node (ref "U1") (pin "39") (pinfunction "P0.0/AD0_39") (pintype "bidirectional"))
    )
    (net (code "6") (name "/P01") (class "Default")
      (node (ref "DS15") (pin "2") (pinfunction "K_2") (pintype "passive"))
      (node (ref "J2") (pin "8") (pinfunction "DB1_8") (pintype "passive"))
      (node (ref "R36") (pin "1") (pinfunction "1_1") (pintype "passive"))
      (node (ref "U1") (pin "38") (pinfunction "P0.1/AD1_38") (pintype "bidirectional"))
    )
    (net (code "7") (name "/P02") (class "Default")
      (node (ref "DS14") (pin "2") (pinfunction "K_2") (pintype "passive"))
      (node (ref "J2") (pin "9") (pinfunction "DB2_9") (pintype "passive"))
      (node (ref "R41") (pin "2") (pinfunction "2_2") (pintype "passive"))
      (node (ref "U1") (pin "37") (pinfunction "P0.2/AD2_37") (pintype "bidirectional"))
    )
    (net (code "8") (name "/P03") (class "Default")
      (node (ref "DS13") (pin "2") (pinfunction "K_2") (pintype "passive"))
      (node (ref "J2") (pin "10") (pinfunction "DB3_10") (pintype "passive"))
      (node (ref "R39") (pin "2") (pinfunction "2_2") (pintype "passive"))
      (node (ref "U1") (pin "36") (pinfunction "P0.3/AD3_36") (pintype "bidirectional"))
    )
    (net (code "9") (name "/P04") (class "Default")
      (node (ref "DS12") (pin "2") (pinfunction "K_2") (pintype "passive"))
      (node (ref "J2") (pin "11") (pinfunction "DB4_11") (pintype "passive"))
      (node (ref "R38") (pin "2") (pinfunction "2_2") (pintype "passive"))
      (node (ref "U1") (pin "35") (pinfunction "P0.4/AD4_35") (pintype "bidirectional"))
    )
    (net (code "10") (name "/P05") (class "Default")
      (node (ref "DS11") (pin "2") (pinfunction "K_2") (pintype "passive"))
      (node (ref "J2") (pin "12") (pinfunction "DB5_12") (pintype "passive"))
      (node (ref "R35") (pin "1") (pinfunction "1_1") (pintype "passive"))
      (node (ref "U1") (pin "34") (pinfunction "P0.5/AD5_34") (pintype "bidirectional"))
    )
    (net (code "11") (name "/P06") (class "Default")
      (node (ref "DS10") (pin "2") (pinfunction "K_2") (pintype "passive"))
      (node (ref "J2") (pin "13") (pinfunction "DB6_13") (pintype "passive"))
      (node (ref "R42") (pin "2") (pinfunction "2_2") (pintype "passive"))
      (node (ref "U1") (pin "33") (pinfunction "P0.6/AD6_33") (pintype "bidirectional"))
    )
    (net (code "12") (name "/P07") (class "Default")
      (node (ref "DS9") (pin "2") (pinfunction "K_2") (pintype "passive"))
      (node (ref "J2") (pin "14") (pinfunction "DB7_14") (pintype "passive"))
      (node (ref "R40") (pin "2") (pinfunction "2_2") (pintype "passive"))
      (node (ref "U1") (pin "32") (pinfunction "P0.7/AD7_32") (pintype "bidirectional"))
    )
    (net (code "13") (name "/P10") (class "Default")
      (node (ref "DS8") (pin "2") (pinfunction "K_2") (pintype "passive"))
      (node (ref "IC2") (pin "7") (pinfunction "7_7") (pintype "passive"))
      (node (ref "IC4") (pin "7") (pinfunction "7_7") (pintype "passive"))
      (node (ref "S12") (pin "1") (pinfunction "1_1") (pintype "passive"))
      (node (ref "S16") (pin "1") (pinfunction "1_1") (pintype "passive"))
      (node (ref "S4") (pin "1") (pinfunction "1_1") (pintype "passive"))
      (node (ref "S8") (pin "1") (pinfunction "1_1") (pintype "passive"))
      (node (ref "U1") (pin "1") (pinfunction "P1.0/T2_1") (pintype "bidirectional"))
    )
    (net (code "14") (name "/P11") (class "Default")
      (node (ref "DS7") (pin "2") (pinfunction "K_2") (pintype "passive"))
      (node (ref "IC2") (pin "5") (pinfunction "5_5") (pintype "passive"))
      (node (ref "IC2") (pin "6") (pinfunction "6_6") (pintype "passive"))
      (node (ref "IC4") (pin "6") (pinfunction "6_6") (pintype "passive"))
      (node (ref "S11") (pin "1") (pinfunction "1_1") (pintype "passive"))
      (node (ref "S15") (pin "1") (pinfunction "1_1") (pintype "passive"))
      (node (ref "S3") (pin "1") (pinfunction "1_1") (pintype "passive"))
      (node (ref "S7") (pin "1") (pinfunction "1_1") (pintype "passive"))
      (node (ref "U1") (pin "2") (pinfunction "P1.1/T2EX_2") (pintype "bidirectional"))
    )
    (net (code "15") (name "/P12") (class "Default")
      (node (ref "DS6") (pin "2") (pinfunction "K_2") (pintype "passive"))
      (node (ref "IC4") (pin "5") (pinfunction "5_5") (pintype "passive"))
      (node (ref "S10") (pin "1") (pinfunction "1_1") (pintype "passive"))
      (node (ref "S14") (pin "1") (pinfunction "1_1") (pintype "passive"))
      (node (ref "S2") (pin "1") (pinfunction "1_1") (pintype "passive"))
      (node (ref "S6") (pin "1") (pinfunction "1_1") (pintype "passive"))
      (node (ref "U1") (pin "3") (pinfunction "P1.2_3") (pintype "bidirectional"))
    )
    (net (code "16") (name "/P13") (class "Default")
      (node (ref "DS5") (pin "2") (pinfunction "K_2") (pintype "passive"))
      (node (ref "S1") (pin "1") (pinfunction "1_1") (pintype "passive"))
      (node (ref "S13") (pin "1") (pinfunction "1_1") (pintype "passive"))
      (node (ref "S5") (pin "1") (pinfunction "1_1") (pintype "passive"))
      (node (ref "S9") (pin "1") (pinfunction "1_1") (pintype "passive"))
      (node (ref "U1") (pin "4") (pinfunction "P1.3_4") (pintype "bidirectional"))
    )
    (net (code "17") (name "/P14") (class "Default")
      (node (ref "DS4") (pin "2") (pinfunction "K_2") (pintype "passive"))
      (node (ref "S13") (pin "2") (pinfunction "2_2") (pintype "passive"))
      (node (ref "S14") (pin "2") (pinfunction "2_2") (pintype "passive"))
      (node (ref "S15") (pin "2") (pinfunction "2_2") (pintype "passive"))
      (node (ref "S16") (pin "2") (pinfunction "2_2") (pintype "passive"))
      (node (ref "S17") (pin "2") (pinfunction "2_2") (pintype "passive"))
      (node (ref "U1") (pin "5") (pinfunction "P1.4_5") (pintype "bidirectional"))
    )
    (net (code "18") (name "/P15") (class "Default")
      (node (ref "DS3") (pin "2") (pinfunction "K_2") (pintype "passive"))
      (node (ref "S10") (pin "2") (pinfunction "2_2") (pintype "passive"))
      (node (ref "S11") (pin "2") (pinfunction "2_2") (pintype "passive"))
      (node (ref "S12") (pin "2") (pinfunction "2_2") (pintype "passive"))
      (node (ref "S18") (pin "2") (pinfunction "2_2") (pintype "passive"))
      (node (ref "S9") (pin "2") (pinfunction "2_2") (pintype "passive"))
      (node (ref "U1") (pin "6") (pinfunction "P1.5_6") (pintype "bidirectional"))
    )
    (net (code "19") (name "/P16") (class "Default")
      (node (ref "S19") (pin "2") (pinfunction "2_2") (pintype "passive"))
      (node (ref "S5") (pin "2") (pinfunction "2_2") (pintype "passive"))
      (node (ref "S6") (pin "2") (pinfunction "2_2") (pintype "passive"))
      (node (ref "S7") (pin "2") (pinfunction "2_2") (pintype "passive"))
      (node (ref "S8") (pin "2") (pinfunction "2_2") (pintype "passive"))
      (node (ref "U1") (pin "7") (pinfunction "P1.6_7") (pintype "bidirectional"))
    )
    (net (code "20") (name "/P17") (class "Default")
      (node (ref "DS1") (pin "2") (pinfunction "K_2") (pintype "passive"))
      (node (ref "S1") (pin "2") (pinfunction "2_2") (pintype "passive"))
      (node (ref "S2") (pin "2") (pinfunction "2_2") (pintype "passive"))
      (node (ref "S20") (pin "2") (pinfunction "2_2") (pintype "passive"))
      (node (ref "S3") (pin "2") (pinfunction "2_2") (pintype "passive"))
      (node (ref "S4") (pin "2") (pinfunction "2_2") (pintype "passive"))
      (node (ref "U1") (pin "8") (pinfunction "P1.7_8") (pintype "bidirectional"))
    )
    (net (code "21") (name "/P20") (class "Default")
      (node (ref "DS32") (pin "2") (pinfunction "K_2") (pintype "passive"))
      (node (ref "J2") (pin "4") (pinfunction "RS_4") (pintype "passive"))
      (node (ref "R47") (pin "2") (pinfunction "2_2") (pintype "passive"))
      (node (ref "U1") (pin "21") (pinfunction "P2.0/A8_21") (pintype "bidirectional"))
    )
    (net (code "22") (name "/P21") (class "Default")
      (node (ref "DS31") (pin "2") (pinfunction "K_2") (pintype "passive"))
      (node (ref "J2") (pin "5") (pinfunction "RW_5") (pintype "passive"))
      (node (ref "R48") (pin "2") (pinfunction "2_2") (pintype "passive"))
      (node (ref "U1") (pin "22") (pinfunction "P2.1/A9_22") (pintype "bidirectional"))
    )
    (net (code "23") (name "/P22") (class "Default")
      (node (ref "DS30") (pin "2") (pinfunction "K_2") (pintype "passive"))
      (node (ref "J2") (pin "6") (pinfunction "E_6") (pintype "passive"))
      (node (ref "R49") (pin "2") (pinfunction "2_2") (pintype "passive"))
      (node (ref "U1") (pin "23") (pinfunction "P2.2/A10_23") (pintype "bidirectional"))
    )
    (net (code "24") (name "/P23") (class "Default")
      (node (ref "DS29") (pin "2") (pinfunction "K_2") (pintype "passive"))
      (node (ref "R50") (pin "2") (pinfunction "2_2") (pintype "passive"))
      (node (ref "U1") (pin "24") (pinfunction "P2.3/A11_24") (pintype "bidirectional"))
    )
    (net (code "25") (name "/P24") (class "Default")
      (node (ref "DS28") (pin "2") (pinfunction "K_2") (pintype "passive"))
      (node (ref "U1") (pin "25") (pinfunction "P2.4/A12_25") (pintype "bidirectional"))
    )
    (net (code "26") (name "/P25") (class "Default")
      (node (ref "DS27") (pin "2") (pinfunction "K_2") (pintype "passive"))
      (node (ref "U1") (pin "26") (pinfunction "P2.5/A13_26") (pintype "bidirectional"))
    )
    (net (code "27") (name "/P26") (class "Default")
      (node (ref "DS26") (pin "2") (pinfunction "K_2") (pintype "passive"))
      (node (ref "U1") (pin "27") (pinfunction "P2.6/A14_27") (pintype "bidirectional"))
    )
    (net (code "28") (name "/P27") (class "Default")
      (node (ref "DS25") (pin "2") (pinfunction "K_2") (pintype "passive"))
      (node (ref "U1") (pin "28") (pinfunction "P2.7/A15_28") (pintype "bidirectional"))
    )
    (net (code "29") (name "/P30") (class "Default")
      (node (ref "DS24") (pin "2") (pinfunction "K_2") (pintype "passive"))
      (node (ref "JP4") (pin "11") (pinfunction "11_11") (pintype "passive"))
      (node (ref "U1") (pin "10") (pinfunction "P3.0/RxD_10") (pintype "bidirectional"))
    )
    (net (code "30") (name "/P31") (class "Default")
      (node (ref "DS23") (pin "2") (pinfunction "K_2") (pintype "passive"))
      (node (ref "JP4") (pin "12") (pinfunction "12_12") (pintype "passive"))
      (node (ref "U1") (pin "11") (pinfunction "P3.1/TxD_11") (pintype "bidirectional"))
    )
    (net (code "31") (name "/P32") (class "Default")
      (node (ref "DS22") (pin "2") (pinfunction "K_2") (pintype "passive"))
      (node (ref "JP2") (pin "1") (pinfunction "1_1") (pintype "passive"))
      (node (ref "U1") (pin "12") (pinfunction "P3.2/~{INT}0_12") (pintype "bidirectional"))
    )
    (net (code "32") (name "/P33") (class "Default")
      (node (ref "DS21") (pin "2") (pinfunction "K_2") (pintype "passive"))
      (node (ref "IC3") (pin "6") (pinfunction "6_6") (pintype "passive"))
      (node (ref "JP1") (pin "2") (pinfunction "2_2") (pintype "passive"))
      (node (ref "U1") (pin "13") (pinfunction "P3.3/~{INT}1_13") (pintype "bidirectional"))
    )
    (net (code "33") (name "/P34") (class "Default")
      (node (ref "DS20") (pin "2") (pinfunction "K_2") (pintype "passive"))
      (node (ref "IC1") (pin "6") (pinfunction "6_6") (pintype "passive"))
      (node (ref "IC2") (pin "1") (pinfunction "1_1") (pintype "passive"))
      (node (ref "IC3") (pin "5") (pinfunction "5_5") (pintype "passive"))
      (node (ref "U1") (pin "14") (pinfunction "P3.4/T0_14") (pintype "bidirectional"))
    )
    (net (code "34") (name "/P35") (class "Default")
      (node (ref "DS19") (pin "2") (pinfunction "K_2") (pintype "passive"))
      (node (ref "IC1") (pin "5") (pinfunction "5_5") (pintype "passive"))
      (node (ref "U1") (pin "15") (pinfunction "P3.5/T1_15") (pintype "bidirectional"))
    )
    (net (code "35") (name "/P36") (class "Default")
      (node (ref "DS18") (pin "2") (pinfunction "K_2") (pintype "passive"))
      (node (ref "IC1") (pin "2") (pinfunction "2_2") (pintype "passive"))
      (node (ref "U1") (pin "16") (pinfunction "P3.6/~{WR}_16") (pintype "bidirectional"))
    )
    (net (code "36") (name "/P37") (class "Default")
      (node (ref "DS17") (pin "2") (pinfunction "K_2") (pintype "passive"))
      (node (ref "IC1") (pin "1") (pinfunction "1_1") (pintype "passive"))
      (node (ref "R33") (pin "2") (pinfunction "2_2") (pintype "passive"))
      (node (ref "U1") (pin "17") (pinfunction "P3.7/~{RD}_17") (pintype "bidirectional"))
    )
    (net (code "37") (name "/RESET") (class "Default")
      (node (ref "C3") (pin "2") (pinfunction "2_2") (pintype "passive"))
      (node (ref "R37") (pin "2") (pinfunction "2_2") (pintype "passive"))
      (node (ref "S21") (pin "1") (pinfunction "1_1") (pintype "passive"))
      (node (ref "U1") (pin "9") (pinfunction "RST_9") (pintype "input"))
    )
    (net (code "38") (name "GND") (class "Default")
      (node (ref "C1") (pin "2") (pinfunction "2_2") (pintype "passive"))
      (node (ref "C2") (pin "2") (pinfunction "2_2") (pintype "passive"))
      (node (ref "C7") (pin "1") (pinfunction "1_1") (pintype "passive"))
      (node (ref "DSP") (pin "2") (pinfunction "K_2") (pintype "passive"))
      (node (ref "IC1") (pin "4") (pinfunction "4_4") (pintype "passive"))
      (node (ref "IC2") (pin "4") (pinfunction "4_4") (pintype "passive"))
      (node (ref "IC3") (pin "1") (pinfunction "1_1") (pintype "passive"))
      (node (ref "IC3") (pin "2") (pinfunction "2_2") (pintype "passive"))
      (node (ref "IC3") (pin "3") (pinfunction "3_3") (pintype "passive"))
      (node (ref "IC3") (pin "4") (pinfunction "4_4") (pintype "passive"))
      (node (ref "IC3") (pin "7") (pinfunction "7_7") (pintype "passive"))
      (node (ref "IC4") (pin "4") (pinfunction "4_4") (pintype "passive"))
      (node (ref "J1") (pin "5") (pinfunction "5_5") (pintype "passive"))
      (node (ref "J2") (pin "1") (pinfunction "GND_1") (pintype "passive"))
      (node (ref "J2") (pin "16") (pinfunction "BG_GND_16") (pintype "passive"))
      (node (ref "J2") (pin "3") (pinfunction "VO_3") (pintype "passive"))
      (node (ref "JP1") (pin "3") (pinfunction "3_3") (pintype "passive"))
      (node (ref "JP2") (pin "4") (pinfunction "4_4") (pintype "passive"))
      (node (ref "JP4") (pin "15") (pinfunction "15_15") (pintype "passive"))
      (node (ref "LS1") (pin "2") (pinfunction "2_2") (pintype "passive"))
      (node (ref "R37") (pin "1") (pinfunction "1_1") (pintype "passive"))
      (node (ref "R43") (pin "1") (pinfunction "1_1") (pintype "passive"))
      (node (ref "S17") (pin "1") (pinfunction "1_1") (pintype "passive"))
      (node (ref "S18") (pin "1") (pinfunction "1_1") (pintype "passive"))
      (node (ref "S19") (pin "1") (pinfunction "1_1") (pintype "passive"))
      (node (ref "S20") (pin "1") (pinfunction "1_1") (pintype "passive"))
      (node (ref "U1") (pin "20") (pinfunction "VSS_20") (pintype "power_in"))
      (node (ref "USB1") (pin "-") (pinfunction "-_-") (pintype "passive"))
    )
    (net (code "39") (name "Net-(C4-Pad1)") (class "Default")
      (node (ref "C4") (pin "1") (pinfunction "1_1") (pintype "passive"))
      (node (ref "JP4") (pin "3") (pinfunction "3_3") (pintype "passive"))
    )
    (net (code "40") (name "Net-(C4-Pad2)") (class "Default")
      (node (ref "C4") (pin "2") (pinfunction "2_2") (pintype "passive"))
      (node (ref "JP4") (pin "1") (pinfunction "1_1") (pintype "passive"))
    )
    (net (code "41") (name "Net-(C5-Pad1)") (class "Default")
      (node (ref "C5") (pin "1") (pinfunction "1_1") (pintype "passive"))
      (node (ref "JP4") (pin "5") (pinfunction "5_5") (pintype "passive"))
    )
    (net (code "42") (name "Net-(C5-Pad2)") (class "Default")
      (node (ref "C5") (pin "2") (pinfunction "2_2") (pintype "passive"))
      (node (ref "JP4") (pin "4") (pinfunction "4_4") (pintype "passive"))
    )
    (net (code "43") (name "Net-(C6-Pad2)") (class "Default")
      (node (ref "C6") (pin "2") (pinfunction "2_2") (pintype "passive"))
      (node (ref "JP4") (pin "2") (pinfunction "2_2") (pintype "passive"))
    )
    (net (code "44") (name "Net-(C7-Pad2)") (class "Default")
      (node (ref "C7") (pin "2") (pinfunction "2_2") (pintype "passive"))
      (node (ref "JP4") (pin "6") (pinfunction "6_6") (pintype "passive"))
    )
    (net (code "45") (name "Net-(DS1-A)") (class "Default")
      (node (ref "DS1") (pin "1") (pinfunction "A_1") (pintype "passive"))
      (node (ref "R1") (pin "2") (pinfunction "2_2") (pintype "passive"))
    )
    (net (code "46") (name "Net-(DS2-A)") (class "Default")
      (node (ref "DS2") (pin "1") (pinfunction "A_1") (pintype "passive"))
      (node (ref "R2") (pin "2") (pinfunction "2_2") (pintype "passive"))
    )
    (net (code "47") (name "Net-(DS3-A)") (class "Default")
      (node (ref "DS3") (pin "1") (pinfunction "A_1") (pintype "passive"))
      (node (ref "R3") (pin "2") (pinfunction "2_2") (pintype "passive"))
    )
    (net (code "48") (name "Net-(DS4-A)") (class "Default")
      (node (ref "DS4") (pin "1") (pinfunction "A_1") (pintype "passive"))
      (node (ref "R4") (pin "2") (pinfunction "2_2") (pintype "passive"))
    )
    (net (code "49") (name "Net-(DS5-A)") (class "Default")
      (node (ref "DS5") (pin "1") (pinfunction "A_1") (pintype "passive"))
      (node (ref "R5") (pin "2") (pinfunction "2_2") (pintype "passive"))
    )
    (net (code "50") (name "Net-(DS6-A)") (class "Default")
      (node (ref "DS6") (pin "1") (pinfunction "A_1") (pintype "passive"))
      (node (ref "R6") (pin "2") (pinfunction "2_2") (pintype "passive"))
    )
    (net (code "51") (name "Net-(DS7-A)") (class "Default")
      (node (ref "DS7") (pin "1") (pinfunction "A_1") (pintype "passive"))
      (node (ref "R7") (pin "2") (pinfunction "2_2") (pintype "passive"))
    )
    (net (code "52") (name "Net-(DS8-A)") (class "Default")
      (node (ref "DS8") (pin "1") (pinfunction "A_1") (pintype "passive"))
      (node (ref "R8") (pin "2") (pinfunction "2_2") (pintype "passive"))
    )
    (net (code "53") (name "Net-(DS9-A)") (class "Default")
      (node (ref "DS9") (pin "1") (pinfunction "A_1") (pintype "passive"))
      (node (ref "R9") (pin "2") (pinfunction "2_2") (pintype "passive"))
    )
    (net (code "54") (name "Net-(DS10-A)") (class "Default")
      (node (ref "DS10") (pin "1") (pinfunction "A_1") (pintype "passive"))
      (node (ref "R10") (pin "2") (pinfunction "2_2") (pintype "passive"))
    )
    (net (code "55") (name "Net-(DS11-A)") (class "Default")
      (node (ref "DS11") (pin "1") (pinfunction "A_1") (pintype "passive"))
      (node (ref "R11") (pin "2") (pinfunction "2_2") (pintype "passive"))
    )
    (net (code "56") (name "Net-(DS12-A)") (class "Default")
      (node (ref "DS12") (pin "1") (pinfunction "A_1") (pintype "passive"))
      (node (ref "R12") (pin "2") (pinfunction "2_2") (pintype "passive"))
    )
    (net (code "57") (name "Net-(DS13-A)") (class "Default")
      (node (ref "DS13") (pin "1") (pinfunction "A_1") (pintype "passive"))
      (node (ref "R13") (pin "2") (pinfunction "2_2") (pintype "passive"))
    )
    (net (code "58") (name "Net-(DS14-A)") (class "Default")
      (node (ref "DS14") (pin "1") (pinfunction "A_1") (pintype "passive"))
      (node (ref "R14") (pin "2") (pinfunction "2_2") (pintype "passive"))
    )
    (net (code "59") (name "Net-(DS15-A)") (class "Default")
      (node (ref "DS15") (pin "1") (pinfunction "A_1") (pintype "passive"))
      (node (ref "R15") (pin "2") (pinfunction "2_2") (pintype "passive"))
    )
    (net (code "60") (name "Net-(DS16-A)") (class "Default")
      (node (ref "DS16") (pin "1") (pinfunction "A_1") (pintype "passive"))
      (node (ref "R16") (pin "2") (pinfunction "2_2") (pintype "passive"))
    )
    (net (code "61") (name "Net-(DS17-A)") (class "Default")
      (node (ref "DS17") (pin "1") (pinfunction "A_1") (pintype "passive"))
      (node (ref "R17") (pin "2") (pinfunction "2_2") (pintype "passive"))
    )
    (net (code "62") (name "Net-(DS18-A)") (class "Default")
      (node (ref "DS18") (pin "1") (pinfunction "A_1") (pintype "passive"))
      (node (ref "R18") (pin "2") (pinfunction "2_2") (pintype "passive"))
    )
    (net (code "63") (name "Net-(DS19-A)") (class "Default")
      (node (ref "DS19") (pin "1") (pinfunction "A_1") (pintype "passive"))
      (node (ref "R19") (pin "2") (pinfunction "2_2") (pintype "passive"))
    )
    (net (code "64") (name "Net-(DS20-A)") (class "Default")
      (node (ref "DS20") (pin "1") (pinfunction "A_1") (pintype "passive"))
      (node (ref "R20") (pin "2") (pinfunction "2_2") (pintype "passive"))
    )
    (net (code "65") (name "Net-(DS21-A)") (class "Default")
      (node (ref "DS21") (pin "1") (pinfunction "A_1") (pintype "passive"))
      (node (ref "R21") (pin "2") (pinfunction "2_2") (pintype "passive"))
    )
    (net (code "66") (name "Net-(DS22-A)") (class "Default")
      (node (ref "DS22") (pin "1") (pinfunction "A_1") (pintype "passive"))
      (node (ref "R22") (pin "2") (pinfunction "2_2") (pintype "passive"))
    )
    (net (code "67") (name "Net-(DS23-A)") (class "Default")
      (node (ref "DS23") (pin "1") (pinfunction "A_1") (pintype "passive"))
      (node (ref "R23") (pin "2") (pinfunction "2_2") (pintype "passive"))
    )
    (net (code "68") (name "Net-(DS24-A)") (class "Default")
      (node (ref "DS24") (pin "1") (pinfunction "A_1") (pintype "passive"))
      (node (ref "R24") (pin "2") (pinfunction "2_2") (pintype "passive"))
    )
    (net (code "69") (name "Net-(DS25-A)") (class "Default")
      (node (ref "DS25") (pin "1") (pinfunction "A_1") (pintype "passive"))
      (node (ref "R25") (pin "2") (pinfunction "2_2") (pintype "passive"))
    )
    (net (code "70") (name "Net-(DS26-A)") (class "Default")
      (node (ref "DS26") (pin "1") (pinfunction "A_1") (pintype "passive"))
      (node (ref "R26") (pin "2") (pinfunction "2_2") (pintype "passive"))
    )
    (net (code "71") (name "Net-(DS27-A)") (class "Default")
      (node (ref "DS27") (pin "1") (pinfunction "A_1") (pintype "passive"))
      (node (ref "R27") (pin "2") (pinfunction "2_2") (pintype "passive"))
    )
    (net (code "72") (name "Net-(DS28-A)") (class "Default")
      (node (ref "DS28") (pin "1") (pinfunction "A_1") (pintype "passive"))
      (node (ref "R28") (pin "2") (pinfunction "2_2") (pintype "passive"))
    )
    (net (code "73") (name "Net-(DS29-A)") (class "Default")
      (node (ref "DS29") (pin "1") (pinfunction "A_1") (pintype "passive"))
      (node (ref "R29") (pin "2") (pinfunction "2_2") (pintype "passive"))
    )
    (net (code "74") (name "Net-(DS30-A)") (class "Default")
      (node (ref "DS30") (pin "1") (pinfunction "A_1") (pintype "passive"))
      (node (ref "R30") (pin "2") (pinfunction "2_2") (pintype "passive"))
    )
    (net (code "75") (name "Net-(DS31-A)") (class "Default")
      (node (ref "DS31") (pin "1") (pinfunction "A_1") (pintype "passive"))
      (node (ref "R31") (pin "2") (pinfunction "2_2") (pintype "passive"))
    )
    (net (code "76") (name "Net-(DS32-A)") (class "Default")
      (node (ref "DS32") (pin "1") (pinfunction "A_1") (pintype "passive"))
      (node (ref "R32") (pin "2") (pinfunction "2_2") (pintype "passive"))
    )
    (net (code "77") (name "Net-(DSP-A)") (class "Default")
      (node (ref "DSP") (pin "1") (pinfunction "A_1") (pintype "passive"))
      (node (ref "RP") (pin "2") (pinfunction "2_2") (pintype "passive"))
    )
    (net (code "78") (name "Net-(DX1-A)") (class "Default")
      (node (ref "DX1") (pin "11") (pinfunction "A_11") (pintype "passive"))
      (node (ref "R34") (pin "2") (pinfunction "2_2") (pintype "passive"))
    )
    (net (code "79") (name "Net-(DX1-B)") (class "Default")
      (node (ref "DX1") (pin "7") (pinfunction "B_7") (pintype "passive"))
      (node (ref "R36") (pin "2") (pinfunction "2_2") (pintype "passive"))
    )
    (net (code "80") (name "Net-(DX1-C)") (class "Default")
      (node (ref "DX1") (pin "4") (pinfunction "C_4") (pintype "passive"))
      (node (ref "R41") (pin "1") (pinfunction "1_1") (pintype "passive"))
    )
    (net (code "81") (name "Net-(DX1-D)") (class "Default")
      (node (ref "DX1") (pin "2") (pinfunction "D_2") (pintype "passive"))
      (node (ref "R39") (pin "1") (pinfunction "1_1") (pintype "passive"))
    )
    (net (code "82") (name "Net-(DX1-DP)") (class "Default")
      (node (ref "DX1") (pin "3") (pinfunction "DP_3") (pintype "passive"))
      (node (ref "R40") (pin "1") (pinfunction "1_1") (pintype "passive"))
    )
    (net (code "83") (name "Net-(DX1-E)") (class "Default")
      (node (ref "DX1") (pin "1") (pinfunction "E_1") (pintype "passive"))
      (node (ref "R38") (pin "1") (pinfunction "1_1") (pintype "passive"))
    )
    (net (code "84") (name "Net-(DX1-F)") (class "Default")
      (node (ref "DX1") (pin "10") (pinfunction "F_10") (pintype "passive"))
      (node (ref "R35") (pin "2") (pinfunction "2_2") (pintype "passive"))
    )
    (net (code "85") (name "Net-(DX1-G)") (class "Default")
      (node (ref "DX1") (pin "5") (pinfunction "G_5") (pintype "passive"))
      (node (ref "R42") (pin "1") (pinfunction "1_1") (pintype "passive"))
    )
    (net (code "86") (name "Net-(IC1-Pad3)") (class "Default")
      (node (ref "IC1") (pin "3") (pinfunction "3_3") (pintype "passive"))
      (node (ref "R44") (pin "1") (pinfunction "1_1") (pintype "passive"))
    )
    (net (code "87") (name "Net-(IC1-Pad7)") (class "Default")
      (node (ref "IC1") (pin "7") (pinfunction "7_7") (pintype "passive"))
      (node (ref "R45") (pin "1") (pinfunction "1_1") (pintype "passive"))
    )
    (net (code "88") (name "Net-(IC1-Pad8)") (class "Default")
      (node (ref "IC1") (pin "8") (pinfunction "8_8") (pintype "passive"))
      (node (ref "JP6") (pin "2") (pinfunction "2_2") (pintype "passive"))
    )
    (net (code "89") (name "Net-(IC2-Pad8)") (class "Default")
      (node (ref "IC2") (pin "8") (pinfunction "8_8") (pintype "passive"))
      (node (ref "JP7") (pin "2") (pinfunction "2_2") (pintype "passive"))
    )
    (net (code "90") (name "Net-(IC3-Pad8)") (class "Default")
      (node (ref "IC3") (pin "8") (pinfunction "8_8") (pintype "passive"))
      (node (ref "JP9") (pin "2") (pinfunction "2_2") (pintype "passive"))
    )
    (net (code "91") (name "Net-(IC4-Pad1)") (class "Default")
      (node (ref "IC4") (pin "1") (pinfunction "1_1") (pintype "passive"))
      (node (ref "JP8") (pin "2") (pinfunction "2_2") (pintype "passive"))
    )
    (net (code "92") (name "Net-(J1-Pad2)") (class "Default")
      (node (ref "J1") (pin "2") (pinfunction "2_2") (pintype "passive"))
      (node (ref "JP4") (pin "14") (pinfunction "14_14") (pintype "passive"))
    )
    (net (code "93") (name "Net-(J1-Pad3)") (class "Default")
      (node (ref "J1") (pin "3") (pinfunction "3_3") (pintype "passive"))
      (node (ref "JP4") (pin "13") (pinfunction "13_13") (pintype "passive"))
    )
    (net (code "94") (name "Net-(J2-BG_VCC)") (class "Default")
      (node (ref "J2") (pin "15") (pinfunction "BG_VCC_15") (pintype "passive"))
      (node (ref "J2") (pin "2") (pinfunction "VCC_2") (pintype "passive"))
      (node (ref "JP10") (pin "2") (pinfunction "2_2") (pintype "passive"))
    )
    (net (code "95") (name "Net-(Q1-B)") (class "Default")
      (node (ref "Q1") (pin "1") (pinfunction "B_1") (pintype "passive"))
      (node (ref "R33") (pin "1") (pinfunction "1_1") (pintype "passive"))
    )
    (net (code "96") (name "Net-(Q1-C)") (class "Default")
      (node (ref "LS1") (pin "1") (pinfunction "1_1") (pintype "passive"))
      (node (ref "Q1") (pin "3") (pinfunction "C_3") (pintype "passive"))
    )
    (net (code "97") (name "Net-(Q1-E)") (class "Default")
      (node (ref "JP3") (pin "2") (pinfunction "2_2") (pintype "passive"))
      (node (ref "Q1") (pin "2") (pinfunction "E_2") (pintype "passive"))
    )
    (net (code "98") (name "Net-(Q2-B)") (class "Default")
      (node (ref "Q2") (pin "1") (pinfunction "B_1") (pintype "passive"))
      (node (ref "R47") (pin "1") (pinfunction "1_1") (pintype "passive"))
    )
    (net (code "99") (name "Net-(Q2-E)") (class "Default")
      (node (ref "JP5") (pin "2") (pinfunction "2_2") (pintype "passive"))
      (node (ref "Q2") (pin "2") (pinfunction "E_2") (pintype "passive"))
      (node (ref "Q3") (pin "2") (pinfunction "E_2") (pintype "passive"))
      (node (ref "Q4") (pin "2") (pinfunction "E_2") (pintype "passive"))
      (node (ref "Q5") (pin "2") (pinfunction "E_2") (pintype "passive"))
    )
    (net (code "100") (name "Net-(Q3-B)") (class "Default")
      (node (ref "Q3") (pin "1") (pinfunction "B_1") (pintype "passive"))
      (node (ref "R48") (pin "1") (pinfunction "1_1") (pintype "passive"))
    )
    (net (code "101") (name "Net-(Q4-B)") (class "Default")
      (node (ref "Q4") (pin "1") (pinfunction "B_1") (pintype "passive"))
      (node (ref "R49") (pin "1") (pinfunction "1_1") (pintype "passive"))
    )
    (net (code "102") (name "Net-(Q5-B)") (class "Default")
      (node (ref "Q5") (pin "1") (pinfunction "B_1") (pintype "passive"))
      (node (ref "R50") (pin "1") (pinfunction "1_1") (pintype "passive"))
    )
    (net (code "103") (name "Net-(R46-BOT)") (class "Default")
      (node (ref "R43") (pin "2") (pinfunction "2_2") (pintype "passive"))
      (node (ref "R46") (pin "2") (pinfunction "BOT_2") (pintype "passive"))
    )
    (net (code "104") (name "Net-(R46-TAP)") (class "Default")
      (node (ref "IC2") (pin "2") (pinfunction "2_2") (pintype "passive"))
      (node (ref "R46") (pin "3") (pinfunction "TAP_3") (pintype "passive"))
    )
    (net (code "105") (name "Net-(U1-XTAL1)") (class "Default")
      (node (ref "C1") (pin "1") (pinfunction "1_1") (pintype "passive"))
      (node (ref "U1") (pin "19") (pinfunction "XTAL1_19") (pintype "input"))
      (node (ref "Y1") (pin "1") (pinfunction "OSC1_1") (pintype "passive"))
    )
    (net (code "106") (name "Net-(U1-XTAL2)") (class "Default")
      (node (ref "C2") (pin "1") (pinfunction "1_1") (pintype "passive"))
      (node (ref "U1") (pin "18") (pinfunction "XTAL2_18") (pintype "output"))
      (node (ref "Y1") (pin "2") (pinfunction "OSC2_2") (pintype "passive"))
    )
    (net (code "107") (name "Net-(Y2-OSC1)") (class "Default")
      (node (ref "IC4") (pin "2") (pinfunction "2_2") (pintype "passive"))
      (node (ref "Y2") (pin "1") (pinfunction "OSC1_1") (pintype "passive"))
    )
    (net (code "108") (name "Net-(Y2-OSC2)") (class "Default")
      (node (ref "IC4") (pin "3") (pinfunction "3_3") (pintype "passive"))
      (node (ref "Y2") (pin "2") (pinfunction "OSC2_2") (pintype "passive"))
    )
    (net (code "109") (name "VCC") (class "Default")
      (node (ref "C3") (pin "1") (pinfunction "1_1") (pintype "passive"))
      (node (ref "C6") (pin "1") (pinfunction "1_1") (pintype "passive"))
      (node (ref "JP1") (pin "1") (pinfunction "1_1") (pintype "passive"))
      (node (ref "JP10") (pin "1") (pinfunction "1_1") (pintype "passive"))
      (node (ref "JP2") (pin "3") (pinfunction "3_3") (pintype "passive"))
      (node (ref "JP3") (pin "1") (pinfunction "1_1") (pintype "passive"))
      (node (ref "JP4") (pin "16") (pinfunction "16_16") (pintype "passive"))
      (node (ref "JP5") (pin "1") (pinfunction "1_1") (pintype "passive"))
      (node (ref "JP6") (pin "1") (pinfunction "1_1") (pintype "passive"))
      (node (ref "JP7") (pin "1") (pinfunction "1_1") (pintype "passive"))
      (node (ref "JP8") (pin "1") (pinfunction "1_1") (pintype "passive"))
      (node (ref "JP9") (pin "1") (pinfunction "1_1") (pintype "passive"))
      (node (ref "R1") (pin "1") (pinfunction "1_1") (pintype "passive"))
      (node (ref "R10") (pin "1") (pinfunction "1_1") (pintype "passive"))
      (node (ref "R11") (pin "1") (pinfunction "1_1") (pintype "passive"))
      (node (ref "R12") (pin "1") (pinfunction "1_1") (pintype "passive"))
      (node (ref "R13") (pin "1") (pinfunction "1_1") (pintype "passive"))
      (node (ref "R14") (pin "1") (pinfunction "1_1") (pintype "passive"))
      (node (ref "R15") (pin "1") (pinfunction "1_1") (pintype "passive"))
      (node (ref "R16") (pin "1") (pinfunction "1_1") (pintype "passive"))
      (node (ref "R17") (pin "1") (pinfunction "1_1") (pintype "passive"))
      (node (ref "R18") (pin "1") (pinfunction "1_1") (pintype "passive"))
      (node (ref "R19") (pin "1") (pinfunction "1_1") (pintype "passive"))
      (node (ref "R2") (pin "1") (pinfunction "1_1") (pintype "passive"))
      (node (ref "R20") (pin "1") (pinfunction "1_1") (pintype "passive"))
      (node (ref "R21") (pin "1") (pinfunction "1_1") (pintype "passive"))
      (node (ref "R22") (pin "1") (pinfunction "1_1") (pintype "passive"))
      (node (ref "R23") (pin "1") (pinfunction "1_1") (pintype "passive"))
      (node (ref "R24") (pin "1") (pinfunction "1_1") (pintype "passive"))
      (node (ref "R25") (pin "1") (pinfunction "1_1") (pintype "passive"))
      (node (ref "R26") (pin "1") (pinfunction "1_1") (pintype "passive"))
      (node (ref "R27") (pin "1") (pinfunction "1_1") (pintype "passive"))
      (node (ref "R28") (pin "1") (pinfunction "1_1") (pintype "passive"))
      (node (ref "R29") (pin "1") (pinfunction "1_1") (pintype "passive"))
      (node (ref "R3") (pin "1") (pinfunction "1_1") (pintype "passive"))
      (node (ref "R30") (pin "1") (pinfunction "1_1") (pintype "passive"))
      (node (ref "R31") (pin "1") (pinfunction "1_1") (pintype "passive"))
      (node (ref "R32") (pin "1") (pinfunction "1_1") (pintype "passive"))
      (node (ref "R4") (pin "1") (pinfunction "1_1") (pintype "passive"))
      (node (ref "R44") (pin "2") (pinfunction "2_2") (pintype "passive"))
      (node (ref "R45") (pin "2") (pinfunction "2_2") (pintype "passive"))
      (node (ref "R46") (pin "1") (pinfunction "TOP_1") (pintype "passive"))
      (node (ref "R5") (pin "1") (pinfunction "1_1") (pintype "passive"))
      (node (ref "R6") (pin "1") (pinfunction "1_1") (pintype "passive"))
      (node (ref "R7") (pin "1") (pinfunction "1_1") (pintype "passive"))
      (node (ref "R8") (pin "1") (pinfunction "1_1") (pintype "passive"))
      (node (ref "R9") (pin "1") (pinfunction "1_1") (pintype "passive"))
      (node (ref "RP") (pin "1") (pinfunction "1_1") (pintype "passive"))
      (node (ref "S21") (pin "2") (pinfunction "2_2") (pintype "passive"))
      (node (ref "U1") (pin "31") (pinfunction "~{EA}/VPP_31") (pintype "input"))
      (node (ref "U1") (pin "40") (pinfunction "VCC_40") (pintype "power_in"))
      (node (ref "USB1") (pin "+") (pinfunction "+_+") (pintype "passive"))
    )
    (net (code "110") (name "unconnected-(DS2-K-Pad2)") (class "Default")
      (node (ref "DS2") (pin "2") (pinfunction "K_2") (pintype "passive"))
    )
    (net (code "111") (name "unconnected-(IC2-Pad3)") (class "Default")
      (node (ref "IC2") (pin "3") (pinfunction "3_3") (pintype "passive"))
    )
    (net (code "112") (name "unconnected-(IC4-Pad8)") (class "Default")
      (node (ref "IC4") (pin "8") (pinfunction "8_8") (pintype "passive"))
    )
    (net (code "113") (name "unconnected-(J1-MH1-Pad10)") (class "Default")
      (node (ref "J1") (pin "10") (pinfunction "MH1_10") (pintype "passive"))
    )
    (net (code "114") (name "unconnected-(J1-MH2-Pad11)") (class "Default")
      (node (ref "J1") (pin "11") (pinfunction "MH2_11") (pintype "passive"))
    )
    (net (code "115") (name "unconnected-(J1-Pad1)") (class "Default")
      (node (ref "J1") (pin "1") (pinfunction "1_1") (pintype "passive"))
    )
    (net (code "116") (name "unconnected-(J1-Pad4)") (class "Default")
      (node (ref "J1") (pin "4") (pinfunction "4_4") (pintype "passive"))
    )
    (net (code "117") (name "unconnected-(J1-Pad6)") (class "Default")
      (node (ref "J1") (pin "6") (pinfunction "6_6") (pintype "passive"))
    )
    (net (code "118") (name "unconnected-(J1-Pad7)") (class "Default")
      (node (ref "J1") (pin "7") (pinfunction "7_7") (pintype "passive"))
    )
    (net (code "119") (name "unconnected-(J1-Pad8)") (class "Default")
      (node (ref "J1") (pin "8") (pinfunction "8_8") (pintype "passive"))
    )
    (net (code "120") (name "unconnected-(J1-Pad9)") (class "Default")
      (node (ref "J1") (pin "9") (pinfunction "9_9") (pintype "passive"))
    )
    (net (code "121") (name "unconnected-(JP2-Pad2)") (class "Default")
      (node (ref "JP2") (pin "2") (pinfunction "2_2") (pintype "passive"))
    )
    (net (code "122") (name "unconnected-(JP4-Pad7)") (class "Default")
      (node (ref "JP4") (pin "7") (pinfunction "7_7") (pintype "passive"))
    )
    (net (code "123") (name "unconnected-(JP4-Pad8)") (class "Default")
      (node (ref "JP4") (pin "8") (pinfunction "8_8") (pintype "passive"))
    )
    (net (code "124") (name "unconnected-(JP4-Pad9)") (class "Default")
      (node (ref "JP4") (pin "9") (pinfunction "9_9") (pintype "passive"))
    )
    (net (code "125") (name "unconnected-(JP4-Pad10)") (class "Default")
      (node (ref "JP4") (pin "10") (pinfunction "10_10") (pintype "passive"))
    )
    (net (code "126") (name "unconnected-(U1-ALE-Pad30)") (class "Default")
      (node (ref "U1") (pin "30") (pinfunction "ALE_30") (pintype "output"))
    )
    (net (code "127") (name "unconnected-(U1-~{PSEN}-Pad29)") (class "Default")
      (node (ref "U1") (pin "29") (pinfunction "~{PSEN}_29") (pintype "output"))
    )
    (net (code "128") (name "unconnected-(USB1-PadD1)") (class "Default")
      (node (ref "USB1") (pin "D1") (pinfunction "D1_D1") (pintype "passive"))
    )
    (net (code "129") (name "unconnected-(USB1-PadD2)") (class "Default")
      (node (ref "USB1") (pin "D2") (pinfunction "D2_D2") (pintype "passive"))
    )
  )
)
